# ME433_PCB.net
KiCad netlist of a schematic drawn in EAGLE
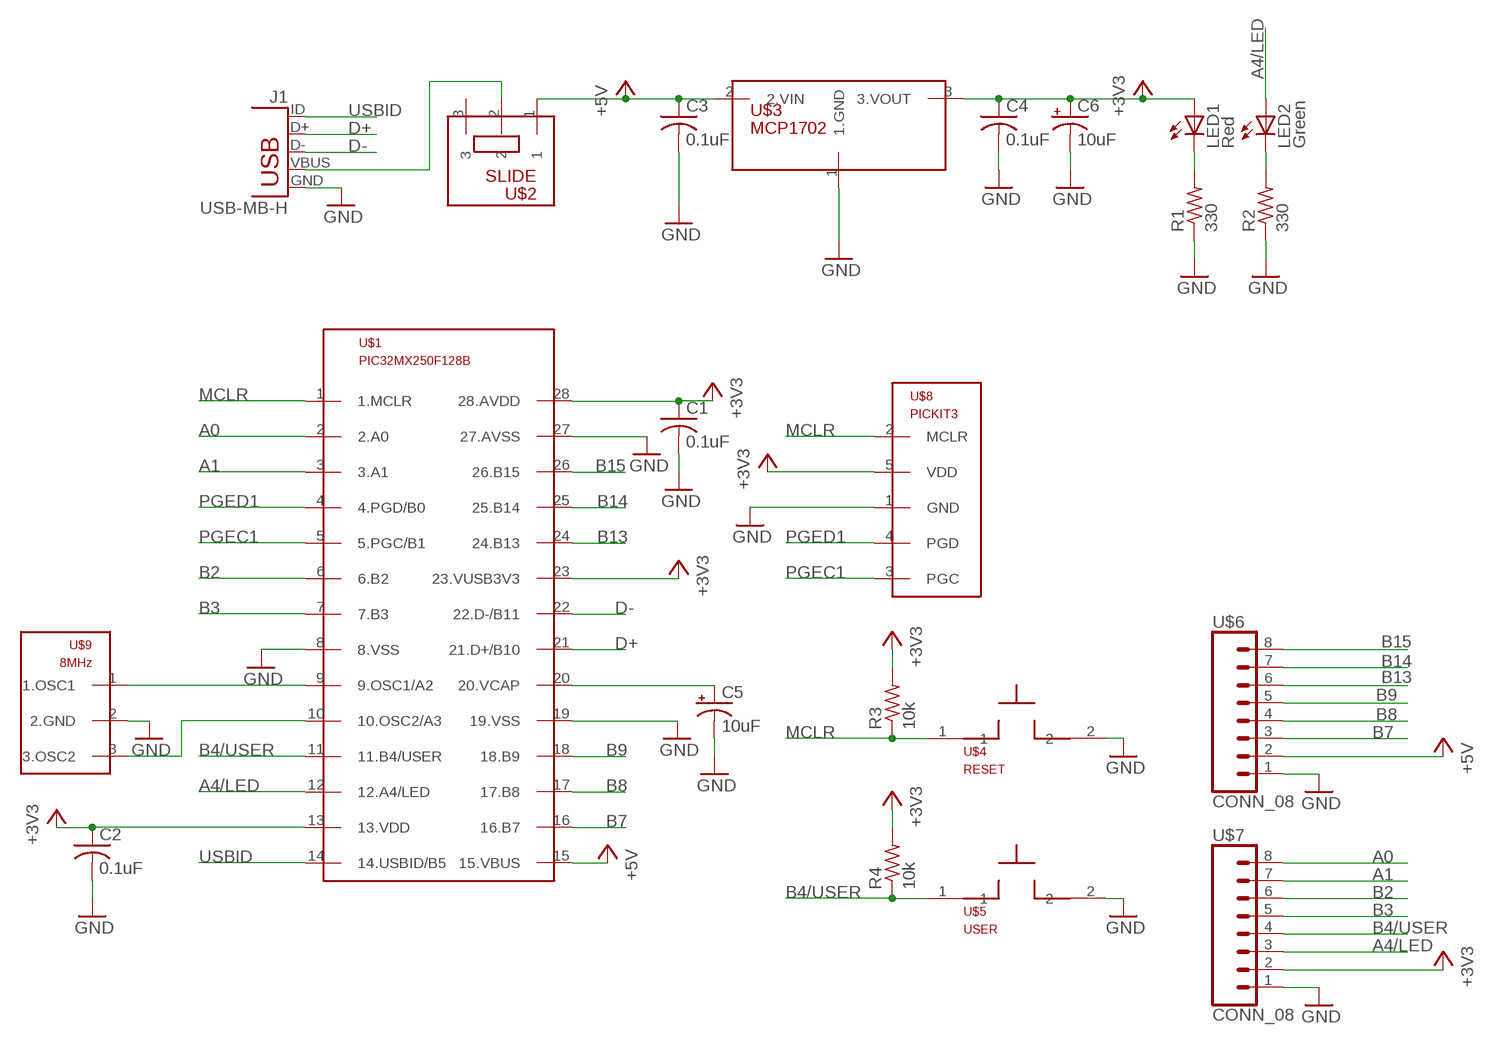
[diagram p0: schematic, sheet 1]

(export (version "E")
  (design (tool "Eeschema 10.0.6"))
  (components
    (comp (ref "C1")
      (value "0.1uF")
      (footprint "eagle-import:C025-025X050")
      (libsource (lib "eagle-import") (part "C-US025-025X050"))
    )
    (comp (ref "C2")
      (value "0.1uF")
      (footprint "eagle-import:C025-025X050")
      (libsource (lib "eagle-import") (part "C-US025-025X050"))
    )
    (comp (ref "C3")
      (value "0.1uF")
      (footprint "eagle-import:C025-025X050")
      (libsource (lib "eagle-import") (part "C-US025-025X050"))
    )
    (comp (ref "C4")
      (value "0.1uF")
      (footprint "eagle-import:C025-025X050")
      (libsource (lib "eagle-import") (part "C-US025-025X050"))
    )
    (comp (ref "C5")
      (value "10uF")
      (footprint "eagle-import:B45181B")
      (libsource (lib "eagle-import") (part "CPOL-USB45181B"))
    )
    (comp (ref "C6")
      (value "10uF")
      (footprint "eagle-import:B45181B")
      (libsource (lib "eagle-import") (part "CPOL-USB45181B"))
    )
    (comp (ref "J1")
      (value "USB-MB-H")
      (footprint "eagle-import:USB-MB-H")
      (libsource (lib "eagle-import") (part "USB-MB-H"))
    )
    (comp (ref "LED1")
      (value "Red")
      (footprint "eagle-import:LED3MM")
      (libsource (lib "eagle-import") (part "LED3MM"))
    )
    (comp (ref "LED2")
      (value "Green")
      (footprint "eagle-import:LED3MM")
      (libsource (lib "eagle-import") (part "LED3MM"))
    )
    (comp (ref "R1")
      (value "330")
      (footprint "eagle-import:0207_10")
      (libsource (lib "eagle-import") (part "R-US_0207/10"))
    )
    (comp (ref "R2")
      (value "330")
      (footprint "eagle-import:0207_10")
      (libsource (lib "eagle-import") (part "R-US_0207/10"))
    )
    (comp (ref "R3")
      (value "10k")
      (footprint "eagle-import:0207_10")
      (libsource (lib "eagle-import") (part "R-US_0207/10"))
    )
    (comp (ref "R4")
      (value "10k")
      (footprint "eagle-import:0207_10")
      (libsource (lib "eagle-import") (part "R-US_0207/10"))
    )
    (comp (ref "U$1")
      (value "PIC32MX250F128B")
      (footprint "eagle-import:DIL28-3")
      (libsource (lib "eagle-import") (part "PIC32MX250F128B"))
    )
    (comp (ref "U$2")
      (value "SLIDE")
      (footprint "eagle-import:SLIDE")
      (libsource (lib "eagle-import") (part "SLIDE"))
    )
    (comp (ref "U$3")
      (value "MCP1702")
      (footprint "eagle-import:TO92")
      (libsource (lib "eagle-import") (part "MCP1702"))
    )
    (comp (ref "U$4")
      (value "RESET")
      (footprint "eagle-import:PB")
      (libsource (lib "eagle-import") (part "PB"))
    )
    (comp (ref "U$5")
      (value "USER")
      (footprint "eagle-import:PB")
      (libsource (lib "eagle-import") (part "PB"))
    )
    (comp (ref "U$6")
      (value "CONN_08")
      (footprint "eagle-import:1X08")
      (libsource (lib "eagle-import") (part "CONN_08"))
    )
    (comp (ref "U$7")
      (value "CONN_08")
      (footprint "eagle-import:1X08")
      (libsource (lib "eagle-import") (part "CONN_08"))
    )
    (comp (ref "U$8")
      (value "PICKIT3")
      (footprint "eagle-import:1X05")
      (libsource (lib "eagle-import") (part "PICKIT3"))
    )
    (comp (ref "U$9")
      (value "8MHz")
      (footprint "eagle-import:OSC")
      (libsource (lib "eagle-import") (part "OSC"))
    )
  )
  (nets
    (net (code "1") (name "+3V3") (class "Default")
      (node (ref "C1") (pin "1") (pinfunction "1_1") (pintype "passive"))
      (node (ref "C2") (pin "1") (pinfunction "1_1") (pintype "passive"))
      (node (ref "C4") (pin "1") (pinfunction "1_1") (pintype "passive"))
      (node (ref "C6") (pin "+") (pinfunction "+_+") (pintype "passive"))
      (node (ref "LED1") (pin "A") (pinfunction "A_A") (pintype "passive"))
      (node (ref "R3") (pin "2") (pinfunction "2_2") (pintype "passive"))
      (node (ref "R4") (pin "2") (pinfunction "2_2") (pintype "passive"))
      (node (ref "U$1") (pin "13") (pinfunction "13.VDD_13") (pintype "bidirectional"))
      (node (ref "U$1") (pin "23") (pinfunction "23.VUSB3V3_23") (pintype "bidirectional"))
      (node (ref "U$1") (pin "28") (pinfunction "28.AVDD_28") (pintype "bidirectional"))
      (node (ref "U$3") (pin "3") (pinfunction "3.VOUT_3") (pintype "bidirectional"))
      (node (ref "U$7") (pin "2") (pinfunction "2_2") (pintype "passive"))
      (node (ref "U$8") (pin "5") (pinfunction "VDD_5") (pintype "bidirectional"))
    )
    (net (code "2") (name "+5V") (class "Default")
      (node (ref "C3") (pin "1") (pinfunction "1_1") (pintype "passive"))
      (node (ref "U$1") (pin "15") (pinfunction "15.VBUS_15") (pintype "bidirectional"))
      (node (ref "U$2") (pin "1") (pinfunction "1_1") (pintype "bidirectional"))
      (node (ref "U$3") (pin "2") (pinfunction "2.VIN_2") (pintype "bidirectional"))
      (node (ref "U$6") (pin "2") (pinfunction "2_2") (pintype "passive"))
    )
    (net (code "3") (name "/A0") (class "Default")
      (node (ref "U$1") (pin "2") (pinfunction "2.A0_2") (pintype "bidirectional"))
      (node (ref "U$7") (pin "8") (pinfunction "8_8") (pintype "passive"))
    )
    (net (code "4") (name "/A1") (class "Default")
      (node (ref "U$1") (pin "3") (pinfunction "3.A1_3") (pintype "bidirectional"))
      (node (ref "U$7") (pin "7") (pinfunction "7_7") (pintype "passive"))
    )
    (net (code "5") (name "/A4{slash}LED") (class "Default")
      (node (ref "LED2") (pin "A") (pinfunction "A_A") (pintype "passive"))
      (node (ref "U$1") (pin "12") (pinfunction "12.A4/LED_12") (pintype "bidirectional"))
      (node (ref "U$7") (pin "3") (pinfunction "3_3") (pintype "passive"))
    )
    (net (code "6") (name "/B2") (class "Default")
      (node (ref "U$1") (pin "6") (pinfunction "6.B2_6") (pintype "bidirectional"))
      (node (ref "U$7") (pin "6") (pinfunction "6_6") (pintype "passive"))
    )
    (net (code "7") (name "/B3") (class "Default")
      (node (ref "U$1") (pin "7") (pinfunction "7.B3_7") (pintype "bidirectional"))
      (node (ref "U$7") (pin "5") (pinfunction "5_5") (pintype "passive"))
    )
    (net (code "8") (name "/B4{slash}USER") (class "Default")
      (node (ref "R4") (pin "1") (pinfunction "1_1") (pintype "passive"))
      (node (ref "U$1") (pin "11") (pinfunction "11.B4/USER_11") (pintype "bidirectional"))
      (node (ref "U$5") (pin "1") (pinfunction "1_1") (pintype "bidirectional"))
      (node (ref "U$7") (pin "4") (pinfunction "4_4") (pintype "passive"))
    )
    (net (code "9") (name "/B7") (class "Default")
      (node (ref "U$1") (pin "16") (pinfunction "16.B7_16") (pintype "bidirectional"))
      (node (ref "U$6") (pin "3") (pinfunction "3_3") (pintype "passive"))
    )
    (net (code "10") (name "/B8") (class "Default")
      (node (ref "U$1") (pin "17") (pinfunction "17.B8_17") (pintype "bidirectional"))
      (node (ref "U$6") (pin "4") (pinfunction "4_4") (pintype "passive"))
    )
    (net (code "11") (name "/B9") (class "Default")
      (node (ref "U$1") (pin "18") (pinfunction "18.B9_18") (pintype "bidirectional"))
      (node (ref "U$6") (pin "5") (pinfunction "5_5") (pintype "passive"))
    )
    (net (code "12") (name "/B13") (class "Default")
      (node (ref "U$1") (pin "24") (pinfunction "24.B13_24") (pintype "bidirectional"))
      (node (ref "U$6") (pin "6") (pinfunction "6_6") (pintype "passive"))
    )
    (net (code "13") (name "/B14") (class "Default")
      (node (ref "U$1") (pin "25") (pinfunction "25.B14_25") (pintype "bidirectional"))
      (node (ref "U$6") (pin "7") (pinfunction "7_7") (pintype "passive"))
    )
    (net (code "14") (name "/B15") (class "Default")
      (node (ref "U$1") (pin "26") (pinfunction "26.B15_26") (pintype "bidirectional"))
      (node (ref "U$6") (pin "8") (pinfunction "8_8") (pintype "passive"))
    )
    (net (code "15") (name "/D+") (class "Default")
      (node (ref "J1") (pin "D+") (pinfunction "D+_D+") (pintype "bidirectional"))
      (node (ref "U$1") (pin "21") (pinfunction "21.D+/B10_21") (pintype "bidirectional"))
    )
    (net (code "16") (name "/D-") (class "Default")
      (node (ref "J1") (pin "D-") (pinfunction "D-_D-") (pintype "bidirectional"))
      (node (ref "U$1") (pin "22") (pinfunction "22.D-/B11_22") (pintype "bidirectional"))
    )
    (net (code "17") (name "/MCLR") (class "Default")
      (node (ref "R3") (pin "1") (pinfunction "1_1") (pintype "passive"))
      (node (ref "U$1") (pin "1") (pinfunction "1.MCLR_1") (pintype "bidirectional"))
      (node (ref "U$4") (pin "1") (pinfunction "1_1") (pintype "bidirectional"))
      (node (ref "U$8") (pin "2") (pinfunction "MCLR_2") (pintype "bidirectional"))
    )
    (net (code "18") (name "/PGEC1") (class "Default")
      (node (ref "U$1") (pin "5") (pinfunction "5.PGC/B1_5") (pintype "bidirectional"))
      (node (ref "U$8") (pin "3") (pinfunction "PGC_3") (pintype "bidirectional"))
    )
    (net (code "19") (name "/PGED1") (class "Default")
      (node (ref "U$1") (pin "4") (pinfunction "4.PGD/B0_4") (pintype "bidirectional"))
      (node (ref "U$8") (pin "4") (pinfunction "PGD_4") (pintype "bidirectional"))
    )
    (net (code "20") (name "/USBID") (class "Default")
      (node (ref "J1") (pin "ID") (pinfunction "ID_ID") (pintype "bidirectional"))
      (node (ref "U$1") (pin "14") (pinfunction "14.USBID/B5_14") (pintype "bidirectional"))
    )
    (net (code "21") (name "GND") (class "Default")
      (node (ref "C1") (pin "2") (pinfunction "2_2") (pintype "passive"))
      (node (ref "C2") (pin "2") (pinfunction "2_2") (pintype "passive"))
      (node (ref "C3") (pin "2") (pinfunction "2_2") (pintype "passive"))
      (node (ref "C4") (pin "2") (pinfunction "2_2") (pintype "passive"))
      (node (ref "C5") (pin "-") (pinfunction "-_-") (pintype "passive"))
      (node (ref "C6") (pin "-") (pinfunction "-_-") (pintype "passive"))
      (node (ref "J1") (pin "GND") (pinfunction "GND_GND") (pintype "bidirectional"))
      (node (ref "R1") (pin "1") (pinfunction "1_1") (pintype "passive"))
      (node (ref "R2") (pin "1") (pinfunction "1_1") (pintype "passive"))
      (node (ref "U$1") (pin "19") (pinfunction "19.VSS_19") (pintype "bidirectional"))
      (node (ref "U$1") (pin "27") (pinfunction "27.AVSS_27") (pintype "bidirectional"))
      (node (ref "U$1") (pin "8") (pinfunction "8.VSS_8") (pintype "bidirectional"))
      (node (ref "U$3") (pin "1") (pinfunction "1.GND_1") (pintype "bidirectional"))
      (node (ref "U$4") (pin "2") (pinfunction "2_2") (pintype "bidirectional"))
      (node (ref "U$5") (pin "2") (pinfunction "2_2") (pintype "bidirectional"))
      (node (ref "U$6") (pin "1") (pinfunction "1_1") (pintype "passive"))
      (node (ref "U$7") (pin "1") (pinfunction "1_1") (pintype "passive"))
      (node (ref "U$8") (pin "1") (pinfunction "GND_1") (pintype "bidirectional"))
      (node (ref "U$9") (pin "2") (pinfunction "2.GND_2") (pintype "bidirectional"))
    )
    (net (code "22") (name "Net-(J1-PadVBUS)") (class "Default")
      (node (ref "J1") (pin "VBUS") (pinfunction "VBUS_VBUS") (pintype "bidirectional"))
      (node (ref "U$2") (pin "2") (pinfunction "2_2") (pintype "bidirectional"))
    )
    (net (code "23") (name "Net-(LED1-C)") (class "Default")
      (node (ref "LED1") (pin "K") (pinfunction "C_K") (pintype "passive"))
      (node (ref "R1") (pin "2") (pinfunction "2_2") (pintype "passive"))
    )
    (net (code "24") (name "Net-(LED2-C)") (class "Default")
      (node (ref "LED2") (pin "K") (pinfunction "C_K") (pintype "passive"))
      (node (ref "R2") (pin "2") (pinfunction "2_2") (pintype "passive"))
    )
    (net (code "25") (name "Net-(U$1-9.OSC1{slash}A2)") (class "Default")
      (node (ref "U$1") (pin "9") (pinfunction "9.OSC1/A2_9") (pintype "bidirectional"))
      (node (ref "U$9") (pin "1") (pinfunction "1.OSC1_1") (pintype "bidirectional"))
    )
    (net (code "26") (name "Net-(U$1-10.OSC2{slash}A3)") (class "Default")
      (node (ref "U$1") (pin "10") (pinfunction "10.OSC2/A3_10") (pintype "bidirectional"))
      (node (ref "U$9") (pin "3") (pinfunction "3.OSC2_3") (pintype "bidirectional"))
    )
    (net (code "27") (name "Net-(U$1-20.VCAP)") (class "Default")
      (node (ref "C5") (pin "+") (pinfunction "+_+") (pintype "passive"))
      (node (ref "U$1") (pin "20") (pinfunction "20.VCAP_20") (pintype "bidirectional"))
    )
    (net (code "28") (name "unconnected-(U$2-Pad3)") (class "Default")
      (node (ref "U$2") (pin "3") (pinfunction "3_3") (pintype "bidirectional"))
    )
  )
)
